# BoardSchematic.net
KiCad netlist of a schematic drawn in Altium Designer
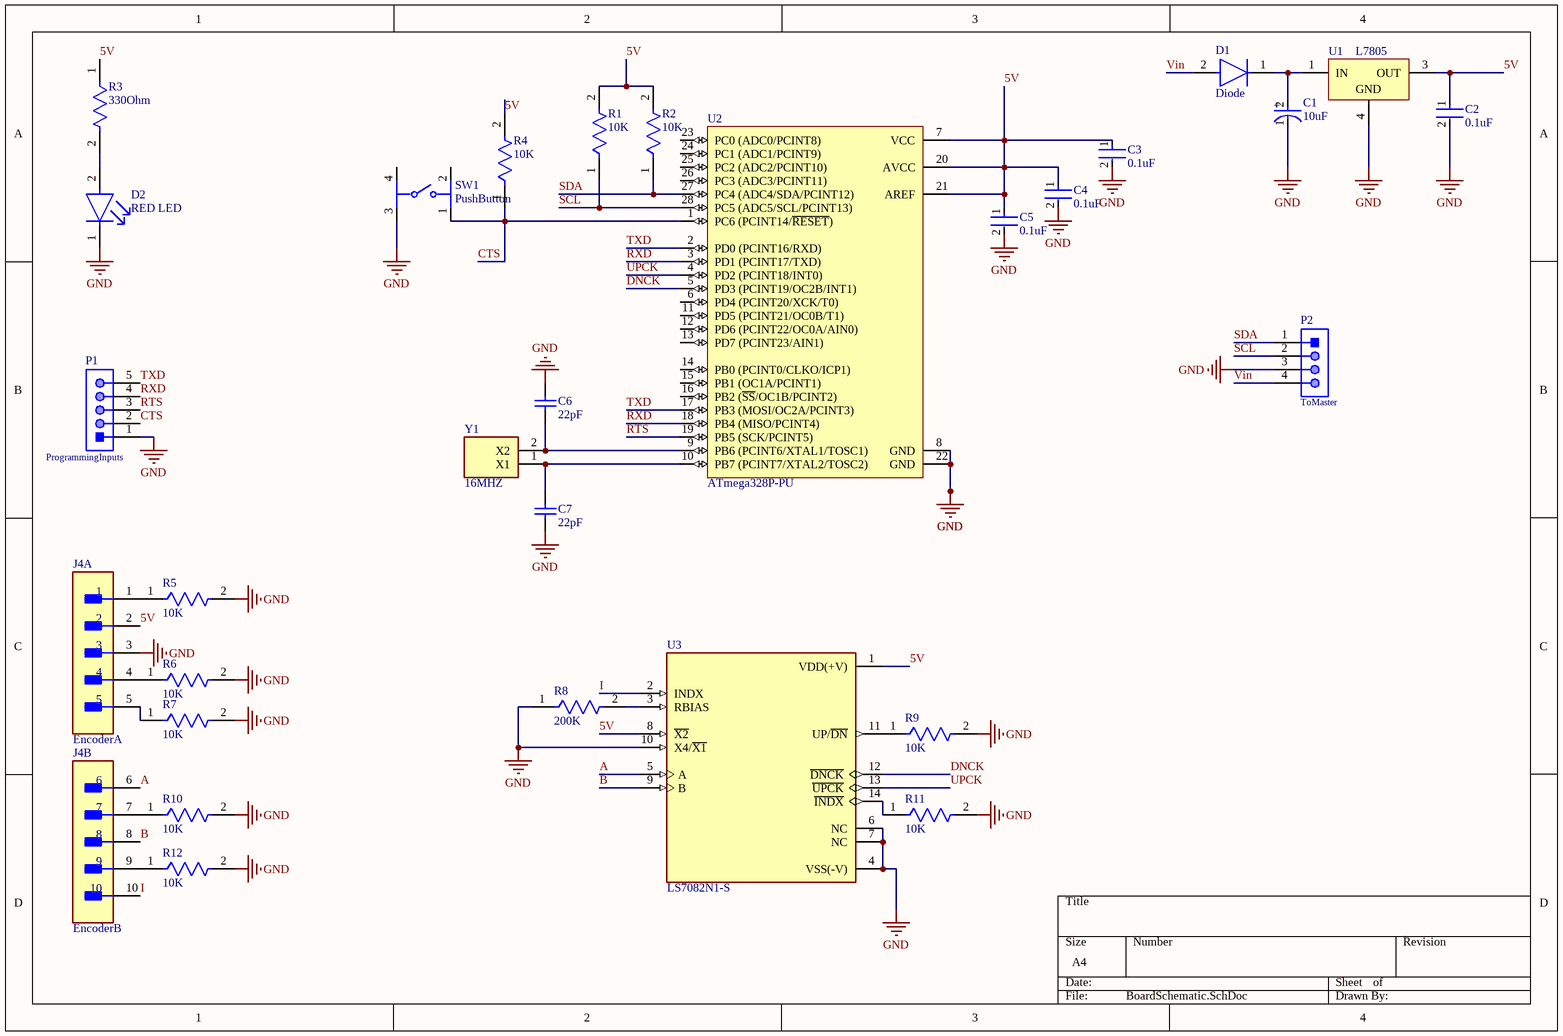
[diagram p0: BoardSchematic.SchDoc]

(export (version "E")
  (design (tool "Eeschema 10.0.6"))
  (components
    (comp (ref "C1")
      (value "10uF")
      (footprint "FP-FKC-MFG")
      (description "CAP ALUM 10UF 20% 50V SMD")
      (fields (field (name "TOLERANCE") "20%") (field (name "VOLTAGE") "50V"))
      (libsource (lib "Altium Content Vault") (part "a00bbbee19879c290e62620ae7e47b1"))
    )
    (comp (ref "C2")
      (value "0.1uF")
      (footprint "FP-C322C104K5R5TA-MFG")
      (description "CAP CER 0.1UF 50V X7R RADIAL")
      (fields (field (name "TOLERANCE") "10%") (field (name "VOLTAGE") "50V"))
      (libsource (lib "Altium Content Vault") (part "b4654b650e69147ec39a6b967a45e02"))
    )
    (comp (ref "C3")
      (value "0.1uF")
      (footprint "FP-K15H5-MFG")
      (description "CAP CER 0.1UF 50V X7R RADIAL")
      (fields (field (name "VOLTAGE") "50V") (field (name "TOLERANCE") "10%"))
      (libsource (lib "Altium Content Vault") (part "11868f565c42a9108669ba33697ecf6"))
    )
    (comp (ref "C4")
      (value "0.1uF")
      (footprint "FP-K15H5-MFG")
      (description "CAP CER 0.1UF 50V X7R RADIAL")
      (fields (field (name "VOLTAGE") "50V") (field (name "TOLERANCE") "10%"))
      (libsource (lib "Altium Content Vault") (part "11868f565c42a9108669ba33697ecf6"))
    )
    (comp (ref "C5")
      (value "0.1uF")
      (footprint "FP-K15H5-MFG")
      (description "CAP CER 0.1UF 50V X7R RADIAL")
      (fields (field (name "VOLTAGE") "50V") (field (name "TOLERANCE") "10%"))
      (libsource (lib "Altium Content Vault") (part "11868f565c42a9108669ba33697ecf6"))
    )
    (comp (ref "C6")
      (value "22pF")
      (footprint "KEMT-C315-THT-2")
      (description "Capacitor, Ceramic, 22 pF, +/-10 %, 100 V, -55 to 125 degC, 2-Pin THD, RoHS, Bulk")
      (libsource (lib "Altium Content Vault") (part "CAP-NP-2"))
    )
    (comp (ref "C7")
      (value "22pF")
      (footprint "KEMT-C315-THT-2")
      (description "Capacitor, Ceramic, 22 pF, +/-10 %, 100 V, -55 to 125 degC, 2-Pin THD, RoHS, Bulk")
      (libsource (lib "Altium Content Vault") (part "CAP-NP-2"))
    )
    (comp (ref "D1")
      (value "Diode")
      (footprint "FP-UF4007-MFG")
      (description "DIODE GEN PURP 1KV 1A DO204AL")
      (fields
        (field (name "MANUFACTURER") "Vishay")
        (field (name "OCTOPART") "https://octopart.com/uf4007-e3%2F54-vishay-42333894")
      )
      (libsource (lib "Altium Content Vault") (part "d7152d700b627762746794eb795d46e"))
    )
    (comp (ref "D2")
      (value "RED LED")
      (footprint "FP-HLMP-1301-MFG")
      (description "LED RED DIFFUSED T-1 T/H")
      (fields
        (field (name "MANUFACTURER PART NUMBER") "HLMP-1301")
        (field (name "OCTOPART") "https://octopart.com/hlmp-1301-broadcom-71130345")
      )
      (libsource (lib "Altium Content Vault") (part "8706943c75ba83719d021d2fdc84c58"))
    )
    (comp (ref "J4")
      (value "EncoderA")
      (footprint "FP-1722981210-MFG")
      (description "CONN HEADER VERT 10POS 3.5MM")
      (fields (field (name "MANUFACTURER") "Molex") (field (name "MANUFACTURER PART NUMBER") "1722981210"))
      (libsource (lib "Altium Content Vault") (part "de255ff815dec4fe6d5caee7def00c9"))
    )
    (comp (ref "P1")
      (value "ProgrammingInputs")
      (footprint "691321100005")
      (description "Serie 3211 - 3.50mm Vertical PCB Header WR-TBL, 5 pin")
      (fields
        (field (name "MANUFACTURER") "Wurth Elektronik")
        (field (name "PART NUMBER") "691321100005")
        (field (name "PUBLISHER") "WurthElektronik")
      )
      (libsource (lib "Altium Content Vault") (part "WE-CN-1P-M-R5"))
    )
    (comp (ref "P2")
      (value "ToMaster")
      (footprint "61300411021")
      (description "THT Angled Pin Header WR-PHD, Pitch 2.54 mm, Single Row, 4 pins")
      (fields
        (field (name "MANUFACTURER") "Wurth Elektronik")
        (field (name "PART NUMBER") "61300411021")
        (field (name "PUBLISHER") "WurthElektronik")
      )
      (libsource (lib "Altium Content Vault") (part "WE-CN-1P-M-R4"))
    )
    (comp (ref "R1")
      (value "10K")
      (footprint "FP-CRCW2512-e3-IPC_A")
      (description "RES Thick Film, 10kΩ, 5%, 1W, 200ppm/°C, 2512")
      (fields (field (name "TOLERANCE") "5%"))
      (libsource (lib "Altium Content Vault") (part "1029c3af85768c4190bb7ad29bc67b5"))
    )
    (comp (ref "R2")
      (value "10K")
      (footprint "FP-CRCW2512-e3-IPC_A")
      (description "RES Thick Film, 10kΩ, 5%, 1W, 200ppm/°C, 2512")
      (fields (field (name "TOLERANCE") "5%"))
      (libsource (lib "Altium Content Vault") (part "1029c3af85768c4190bb7ad29bc67b5"))
    )
    (comp (ref "R3")
      (value "330Ohm")
      (footprint "FP-CRCW2010-e3-MFG")
      (description "RES Thick Film, 330Ω, 5%, 0.75W, 200ppm/°C, 2010")
      (fields (field (name "TOLERANCE") "5%"))
      (libsource (lib "Altium Content Vault") (part "1029c3af85768c4190bb7ad29bc67b5"))
    )
    (comp (ref "R4")
      (value "10K")
      (footprint "FP-CRCW2512-e3-IPC_A")
      (description "RES Thick Film, 10kΩ, 5%, 1W, 200ppm/°C, 2512")
      (fields (field (name "TOLERANCE") "5%"))
      (libsource (lib "Altium Content Vault") (part "1029c3af85768c4190bb7ad29bc67b5"))
    )
    (comp (ref "R5")
      (value "10K")
      (footprint "FP-CRCW2512-e3-IPC_A")
      (description "RES Thick Film, 10kΩ, 5%, 1W, 200ppm/°C, 2512")
      (fields (field (name "TOLERANCE") "5%"))
      (libsource (lib "Altium Content Vault") (part "1029c3af85768c4190bb7ad29bc67b5"))
    )
    (comp (ref "R6")
      (value "10K")
      (footprint "FP-CRCW2512-e3-IPC_A")
      (description "RES Thick Film, 10kΩ, 5%, 1W, 200ppm/°C, 2512")
      (fields (field (name "TOLERANCE") "5%"))
      (libsource (lib "Altium Content Vault") (part "1029c3af85768c4190bb7ad29bc67b5"))
    )
    (comp (ref "R7")
      (value "10K")
      (footprint "FP-CRCW2512-e3-IPC_A")
      (description "RES Thick Film, 10kΩ, 5%, 1W, 200ppm/°C, 2512")
      (fields (field (name "TOLERANCE") "5%"))
      (libsource (lib "Altium Content Vault") (part "1029c3af85768c4190bb7ad29bc67b5"))
    )
    (comp (ref "R8")
      (value "200K")
      (footprint "FP-CRCW2512-e3-IPC_B")
      (description "RES Thick Film, 200kΩ, 5%, 1W, 200ppm/°C, 2512")
      (fields (field (name "TOLERANCE") "5%"))
      (libsource (lib "Altium Content Vault") (part "1029c3af85768c4190bb7ad29bc67b5"))
    )
    (comp (ref "R9")
      (value "10K")
      (footprint "FP-CRCW2512-e3-IPC_A")
      (description "RES Thick Film, 10kΩ, 5%, 1W, 200ppm/°C, 2512")
      (fields (field (name "TOLERANCE") "5%"))
      (libsource (lib "Altium Content Vault") (part "1029c3af85768c4190bb7ad29bc67b5"))
    )
    (comp (ref "R10")
      (value "10K")
      (footprint "FP-CRCW2512-e3-IPC_A")
      (description "RES Thick Film, 10kΩ, 5%, 1W, 200ppm/°C, 2512")
      (fields (field (name "TOLERANCE") "5%"))
      (libsource (lib "Altium Content Vault") (part "1029c3af85768c4190bb7ad29bc67b5"))
    )
    (comp (ref "R11")
      (value "10K")
      (footprint "FP-CRCW2512-e3-IPC_A")
      (description "RES Thick Film, 10kΩ, 5%, 1W, 200ppm/°C, 2512")
      (fields (field (name "TOLERANCE") "5%"))
      (libsource (lib "Altium Content Vault") (part "1029c3af85768c4190bb7ad29bc67b5"))
    )
    (comp (ref "R12")
      (value "10K")
      (footprint "FP-CRCW2512-e3-IPC_A")
      (description "RES Thick Film, 10kΩ, 5%, 1W, 200ppm/°C, 2512")
      (fields (field (name "TOLERANCE") "5%"))
      (libsource (lib "Altium Content Vault") (part "1029c3af85768c4190bb7ad29bc67b5"))
    )
    (comp (ref "SW1")
      (value "PushButton")
      (footprint "FP-FSM103-MFG")
      (description "SWITCH TACTILE SPST-NO 0.05A 24V")
      (libsource (lib "Altium Content Vault") (part "c0df99d12937e9d2da15afdedf14b17"))
    )
    (comp (ref "U1")
      (value "L7805")
      (footprint "TO-263_M")
      (description "Positive Voltage Regulator, 3-Pin D2PAK, Tape and Reel")
      (libsource (lib "Altium Content Vault") (part "PM-REG-L4940-SOT3"))
    )
    (comp (ref "U2")
      (value "ATmega328P-PU")
      (footprint "28P3")
      (libsource (lib "Altium Content Vault") (part "MC-8B-ATM48-IL28"))
    )
    (comp (ref "U3")
      (value "LS7082N1-S")
      (footprint "LS7082N1-S:SOIC127P600X175-14N")
      (fields (field (name "MF") "{'manufacturer': u'LSI/CSI'}"))
      (libsource (lib "*") (part "LS7082N1-S"))
    )
    (comp (ref "Y1")
      (value "16MHZ")
      (footprint "SamacSys:ABL16000MHZB2")
      (description "Crystal or Oscillator")
      (fields
        (field (name "MANUFACTURER_PART_NUMBER") "ABL-16.000MHZ-B2")
        (field (name "MOUSER PART NUMBER") "815-ABL-16-B2")
      )
      (libsource (lib "*") (part "ABL-16.000MHZ-B2"))
    )
  )
  (nets
    (net (code "1") (name "/5V") (class "Default")
      (node (ref "C2") (pin "1") (pinfunction "1_1") (pintype "passive"))
      (node (ref "C3") (pin "1") (pinfunction "1_1") (pintype "passive"))
      (node (ref "C4") (pin "1") (pinfunction "1_1") (pintype "passive"))
      (node (ref "C5") (pin "1") (pinfunction "1_1") (pintype "passive"))
      (node (ref "J4") (pin "2") (pinfunction "2_2") (pintype "passive"))
      (node (ref "R1") (pin "2") (pinfunction "2_2") (pintype "passive"))
      (node (ref "R2") (pin "2") (pinfunction "2_2") (pintype "passive"))
      (node (ref "R3") (pin "1") (pinfunction "1_1") (pintype "passive"))
      (node (ref "R4") (pin "2") (pinfunction "2_2") (pintype "passive"))
      (node (ref "U1") (pin "3") (pinfunction "OUT_3") (pintype "power_in"))
      (node (ref "U2") (pin "20") (pinfunction "AVCC_20") (pintype "power_in"))
      (node (ref "U2") (pin "21") (pinfunction "AREF_21") (pintype "power_in"))
      (node (ref "U2") (pin "7") (pinfunction "VCC_7") (pintype "power_in"))
      (node (ref "U3") (pin "1") (pinfunction "VDD(+V)_1") (pintype "power_in"))
      (node (ref "U3") (pin "8") (pinfunction "~{X2}_8") (pintype "input"))
    )
    (net (code "2") (name "/A") (class "Default")
      (node (ref "J4") (pin "6") (pinfunction "6_6") (pintype "passive"))
      (node (ref "U3") (pin "5") (pinfunction "A_5") (pintype "input"))
    )
    (net (code "3") (name "/B") (class "Default")
      (node (ref "J4") (pin "8") (pinfunction "8_8") (pintype "passive"))
      (node (ref "U3") (pin "9") (pinfunction "B_9") (pintype "input"))
    )
    (net (code "4") (name "/CTS") (class "Default")
      (node (ref "P1") (pin "2") (pinfunction "2_2") (pintype "passive"))
      (node (ref "R4") (pin "1") (pinfunction "1_1") (pintype "passive"))
      (node (ref "SW1") (pin "1") (pinfunction "1_1") (pintype "passive"))
      (node (ref "U2") (pin "1") (pinfunction "PC6_(PCINT14/~{RESET})_1") (pintype "bidirectional"))
    )
    (net (code "5") (name "/DNCK") (class "Default")
      (node (ref "U2") (pin "5") (pinfunction "PD3_(PCINT19/OC2B/INT1)_5") (pintype "bidirectional"))
      (node (ref "U3") (pin "12") (pinfunction "~{DNCK}_12") (pintype "output"))
    )
    (net (code "6") (name "/I") (class "Default")
      (node (ref "J4") (pin "10") (pinfunction "10_10") (pintype "passive"))
      (node (ref "U3") (pin "2") (pinfunction "INDX_2") (pintype "input"))
    )
    (net (code "7") (name "/RTS") (class "Default")
      (node (ref "P1") (pin "3") (pinfunction "3_3") (pintype "passive"))
      (node (ref "U2") (pin "19") (pinfunction "PB5_(SCK/PCINT5)_19") (pintype "bidirectional"))
    )
    (net (code "8") (name "/RXD") (class "Default")
      (node (ref "P1") (pin "4") (pinfunction "4_4") (pintype "passive"))
      (node (ref "U2") (pin "18") (pinfunction "PB4_(MISO/PCINT4)_18") (pintype "bidirectional"))
      (node (ref "U2") (pin "3") (pinfunction "PD1_(PCINT17/TXD)_3") (pintype "bidirectional"))
    )
    (net (code "9") (name "/SCL") (class "Default")
      (node (ref "P2") (pin "2") (pinfunction "2_2") (pintype "passive"))
      (node (ref "R1") (pin "1") (pinfunction "1_1") (pintype "passive"))
      (node (ref "U2") (pin "28") (pinfunction "PC5_(ADC5/SCL/PCINT13)_28") (pintype "bidirectional"))
    )
    (net (code "10") (name "/SDA") (class "Default")
      (node (ref "P2") (pin "1") (pinfunction "1_1") (pintype "passive"))
      (node (ref "R2") (pin "1") (pinfunction "1_1") (pintype "passive"))
      (node (ref "U2") (pin "27") (pinfunction "PC4_(ADC4/SDA/PCINT12)_27") (pintype "bidirectional"))
    )
    (net (code "11") (name "/TXD") (class "Default")
      (node (ref "P1") (pin "5") (pinfunction "5_5") (pintype "passive"))
      (node (ref "U2") (pin "17") (pinfunction "PB3_(MOSI/OC2A/PCINT3)_17") (pintype "bidirectional"))
      (node (ref "U2") (pin "2") (pinfunction "PD0_(PCINT16/RXD)_2") (pintype "bidirectional"))
    )
    (net (code "12") (name "/UPCK") (class "Default")
      (node (ref "U2") (pin "4") (pinfunction "PD2_(PCINT18/INT0)_4") (pintype "bidirectional"))
      (node (ref "U3") (pin "13") (pinfunction "~{UPCK}_13") (pintype "output"))
    )
    (net (code "13") (name "/Vin") (class "Default")
      (node (ref "D1") (pin "2") (pinfunction "A_2") (pintype "passive"))
      (node (ref "P2") (pin "4") (pinfunction "4_4") (pintype "passive"))
    )
    (net (code "14") (name "GND") (class "Default")
      (node (ref "C1") (pin "1") (pinfunction "C_1") (pintype "passive"))
      (node (ref "C2") (pin "2") (pinfunction "2_2") (pintype "passive"))
      (node (ref "C3") (pin "2") (pinfunction "2_2") (pintype "passive"))
      (node (ref "C4") (pin "2") (pinfunction "2_2") (pintype "passive"))
      (node (ref "C5") (pin "2") (pinfunction "2_2") (pintype "passive"))
      (node (ref "C6") (pin "2") (pinfunction "2_2") (pintype "passive"))
      (node (ref "C7") (pin "1") (pinfunction "1_1") (pintype "passive"))
      (node (ref "D2") (pin "1") (pinfunction "C_1") (pintype "passive"))
      (node (ref "J4") (pin "3") (pinfunction "3_3") (pintype "passive"))
      (node (ref "P1") (pin "1") (pinfunction "1_1") (pintype "passive"))
      (node (ref "P2") (pin "3") (pinfunction "3_3") (pintype "passive"))
      (node (ref "R10") (pin "2") (pinfunction "2_2") (pintype "passive"))
      (node (ref "R11") (pin "2") (pinfunction "2_2") (pintype "passive"))
      (node (ref "R12") (pin "2") (pinfunction "2_2") (pintype "passive"))
      (node (ref "R5") (pin "2") (pinfunction "2_2") (pintype "passive"))
      (node (ref "R6") (pin "2") (pinfunction "2_2") (pintype "passive"))
      (node (ref "R7") (pin "2") (pinfunction "2_2") (pintype "passive"))
      (node (ref "R8") (pin "1") (pinfunction "1_1") (pintype "passive"))
      (node (ref "R9") (pin "2") (pinfunction "2_2") (pintype "passive"))
      (node (ref "SW1") (pin "3") (pinfunction "3_3") (pintype "passive"))
      (node (ref "U1") (pin "4") (pinfunction "GND_4") (pintype "power_in"))
      (node (ref "U2") (pin "22") (pinfunction "GND_22") (pintype "power_in"))
      (node (ref "U2") (pin "8") (pinfunction "GND_8") (pintype "power_in"))
      (node (ref "U3") (pin "10") (pinfunction "X4/~{X1}_10") (pintype "input"))
      (node (ref "U3") (pin "4") (pinfunction "VSS(-V)_4") (pintype "power_in"))
      (node (ref "U3") (pin "6") (pinfunction "NC_6") (pintype "passive"))
      (node (ref "U3") (pin "7") (pinfunction "NC_7") (pintype "passive"))
    )
    (net (code "15") (name "Net-(C1-A)") (class "Default")
      (node (ref "C1") (pin "2") (pinfunction "A_2") (pintype "passive"))
      (node (ref "D1") (pin "1") (pinfunction "C_1") (pintype "passive"))
      (node (ref "U1") (pin "1") (pinfunction "IN_1") (pintype "power_in"))
    )
    (net (code "16") (name "Net-(D2-A)") (class "Default")
      (node (ref "D2") (pin "2") (pinfunction "A_2") (pintype "passive"))
      (node (ref "R3") (pin "2") (pinfunction "2_2") (pintype "passive"))
    )
    (net (code "17") (name "Net-(J4-Pad1)") (class "Default")
      (node (ref "J4") (pin "1") (pinfunction "1_1") (pintype "passive"))
      (node (ref "R5") (pin "1") (pinfunction "1_1") (pintype "passive"))
    )
    (net (code "18") (name "Net-(J4-Pad4)") (class "Default")
      (node (ref "J4") (pin "4") (pinfunction "4_4") (pintype "passive"))
      (node (ref "R6") (pin "1") (pinfunction "1_1") (pintype "passive"))
    )
    (net (code "19") (name "Net-(J4-Pad5)") (class "Default")
      (node (ref "J4") (pin "5") (pinfunction "5_5") (pintype "passive"))
      (node (ref "R7") (pin "1") (pinfunction "1_1") (pintype "passive"))
    )
    (net (code "20") (name "Net-(J4-Pad7)") (class "Default")
      (node (ref "J4") (pin "7") (pinfunction "7_7") (pintype "passive"))
      (node (ref "R10") (pin "1") (pinfunction "1_1") (pintype "passive"))
    )
    (net (code "21") (name "Net-(J4-Pad9)") (class "Default")
      (node (ref "J4") (pin "9") (pinfunction "9_9") (pintype "passive"))
      (node (ref "R12") (pin "1") (pinfunction "1_1") (pintype "passive"))
    )
    (net (code "22") (name "Net-(U2-PB6_(PCINT6{slash}XTAL1{slash}TOSC1))") (class "Default")
      (node (ref "C6") (pin "1") (pinfunction "1_1") (pintype "passive"))
      (node (ref "U2") (pin "9") (pinfunction "PB6_(PCINT6/XTAL1/TOSC1)_9") (pintype "bidirectional"))
      (node (ref "Y1") (pin "2") (pinfunction "X2_2") (pintype "passive"))
    )
    (net (code "23") (name "Net-(U2-PB7_(PCINT7{slash}XTAL2{slash}TOSC2))") (class "Default")
      (node (ref "C7") (pin "2") (pinfunction "2_2") (pintype "passive"))
      (node (ref "U2") (pin "10") (pinfunction "PB7_(PCINT7/XTAL2/TOSC2)_10") (pintype "bidirectional"))
      (node (ref "Y1") (pin "1") (pinfunction "X1_1") (pintype "passive"))
    )
    (net (code "24") (name "Net-(U3-RBIAS)") (class "Default")
      (node (ref "R8") (pin "2") (pinfunction "2_2") (pintype "passive"))
      (node (ref "U3") (pin "3") (pinfunction "RBIAS_3") (pintype "input"))
    )
    (net (code "25") (name "Net-(U3-UP{slash}~{DN})") (class "Default")
      (node (ref "R9") (pin "1") (pinfunction "1_1") (pintype "passive"))
      (node (ref "U3") (pin "11") (pinfunction "UP/~{DN}_11") (pintype "output"))
    )
    (net (code "26") (name "Net-(U3-~{INDX})") (class "Default")
      (node (ref "R11") (pin "1") (pinfunction "1_1") (pintype "passive"))
      (node (ref "U3") (pin "14") (pinfunction "~{INDX}_14") (pintype "output"))
    )
    (net (code "27") (name "unconnected-(SW1-Pad2)") (class "Default")
      (node (ref "SW1") (pin "2") (pinfunction "2_2") (pintype "passive"))
    )
    (net (code "28") (name "unconnected-(SW1-Pad4)") (class "Default")
      (node (ref "SW1") (pin "4") (pinfunction "4_4") (pintype "passive"))
    )
    (net (code "29") (name "unconnected-(U2-PB0_(PCINT0{slash}CLKO{slash}ICP1)-Pad14)") (class "Default")
      (node (ref "U2") (pin "14") (pinfunction "PB0_(PCINT0/CLKO/ICP1)_14") (pintype "bidirectional"))
    )
    (net (code "30") (name "unconnected-(U2-PB1_(OC1A{slash}PCINT1)-Pad15)") (class "Default")
      (node (ref "U2") (pin "15") (pinfunction "PB1_(OC1A/PCINT1)_15") (pintype "bidirectional"))
    )
    (net (code "31") (name "unconnected-(U2-PB2_(~{SS}{slash}OC1B{slash}PCINT2)-Pad16)") (class "Default")
      (node (ref "U2") (pin "16") (pinfunction "PB2_(~{SS}/OC1B/PCINT2)_16") (pintype "bidirectional"))
    )
    (net (code "32") (name "unconnected-(U2-PC0_(ADC0{slash}PCINT8)-Pad23)") (class "Default")
      (node (ref "U2") (pin "23") (pinfunction "PC0_(ADC0/PCINT8)_23") (pintype "bidirectional"))
    )
    (net (code "33") (name "unconnected-(U2-PC1_(ADC1{slash}PCINT9)-Pad24)") (class "Default")
      (node (ref "U2") (pin "24") (pinfunction "PC1_(ADC1/PCINT9)_24") (pintype "bidirectional"))
    )
    (net (code "34") (name "unconnected-(U2-PC2_(ADC2{slash}PCINT10)-Pad25)") (class "Default")
      (node (ref "U2") (pin "25") (pinfunction "PC2_(ADC2/PCINT10)_25") (pintype "bidirectional"))
    )
    (net (code "35") (name "unconnected-(U2-PC3_(ADC3{slash}PCINT11)-Pad26)") (class "Default")
      (node (ref "U2") (pin "26") (pinfunction "PC3_(ADC3/PCINT11)_26") (pintype "bidirectional"))
    )
    (net (code "36") (name "unconnected-(U2-PD4_(PCINT20{slash}XCK{slash}T0)-Pad6)") (class "Default")
      (node (ref "U2") (pin "6") (pinfunction "PD4_(PCINT20/XCK/T0)_6") (pintype "bidirectional"))
    )
    (net (code "37") (name "unconnected-(U2-PD5_(PCINT21{slash}OC0B{slash}T1)-Pad11)") (class "Default")
      (node (ref "U2") (pin "11") (pinfunction "PD5_(PCINT21/OC0B/T1)_11") (pintype "bidirectional"))
    )
    (net (code "38") (name "unconnected-(U2-PD6_(PCINT22{slash}OC0A{slash}AIN0)-Pad12)") (class "Default")
      (node (ref "U2") (pin "12") (pinfunction "PD6_(PCINT22/OC0A/AIN0)_12") (pintype "bidirectional"))
    )
    (net (code "39") (name "unconnected-(U2-PD7_(PCINT23{slash}AIN1)-Pad13)") (class "Default")
      (node (ref "U2") (pin "13") (pinfunction "PD7_(PCINT23/AIN1)_13") (pintype "bidirectional"))
    )
  )
)
